# Connectors.net
KiCad netlist of a schematic drawn in Altium Designer
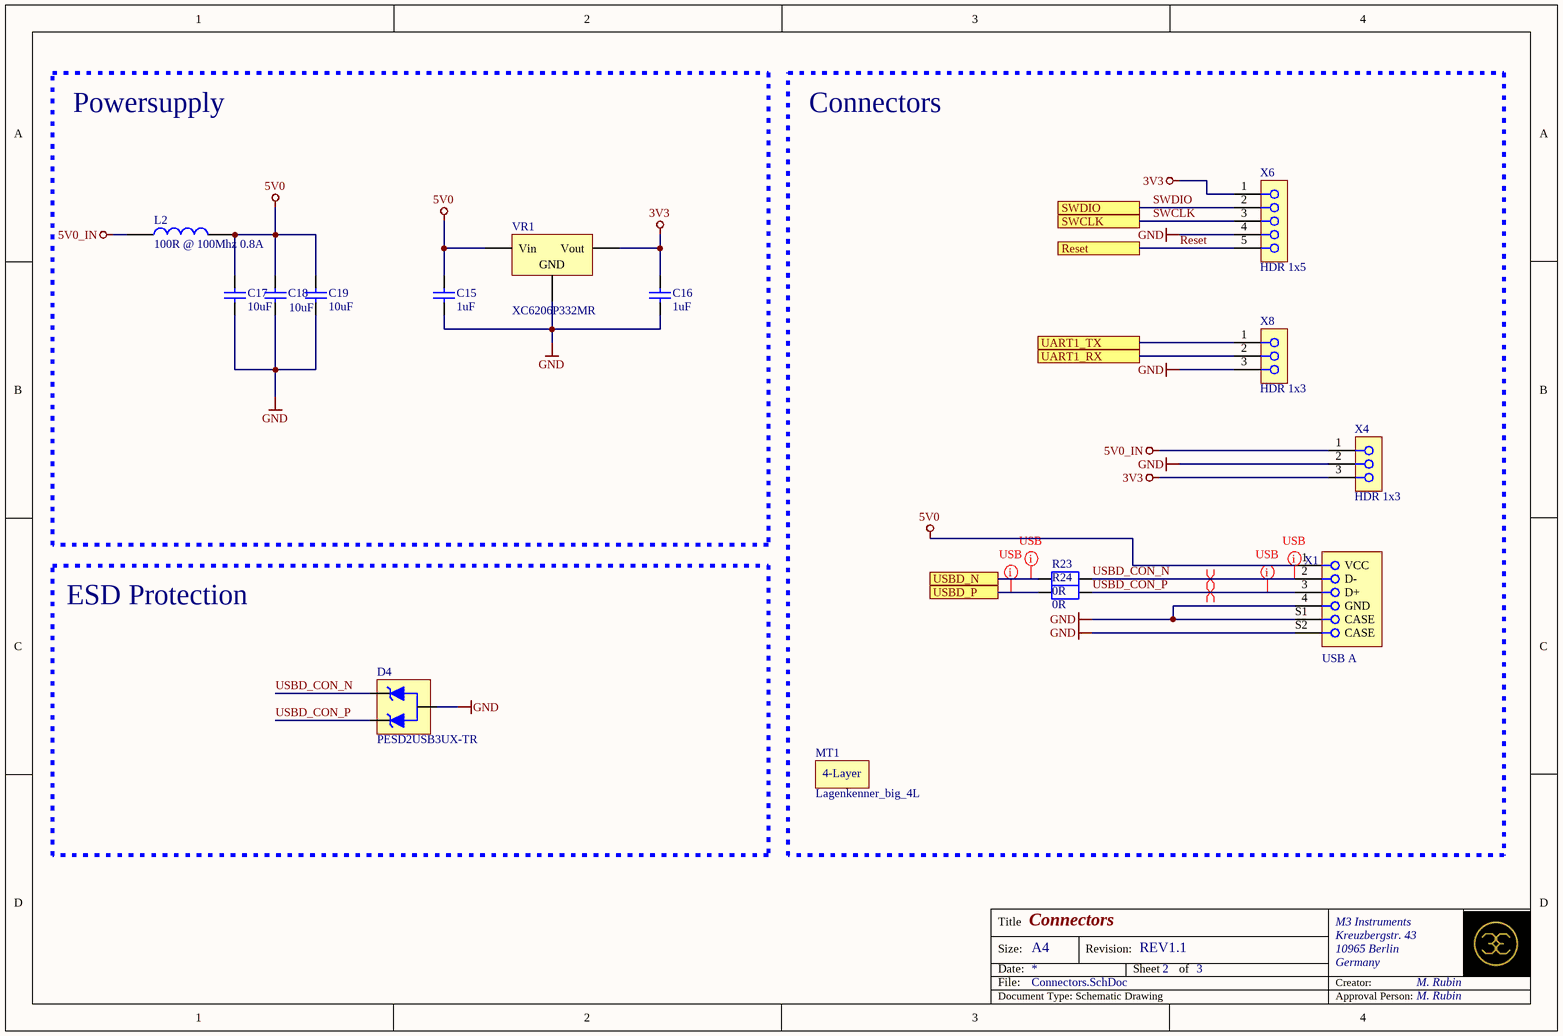
[diagram p0: Connectors.SchDoc]

(export (version "E")
  (design (tool "Eeschema 10.0.6"))
  (components
    (comp (ref "C15")
      (value "1uF")
      (footprint "0603_C")
      (description "Chip capacitors")
      (fields
        (field (name "MANUFACTURER") "Samsung Electro-Mechanics")
        (field (name "PARTNUMBER") "CL10A105KB8NNNC")
      )
      (libsource (lib "Cap") (part "0603 1uF (105) 10% 50V"))
    )
    (comp (ref "C16")
      (value "1uF")
      (footprint "0603_C")
      (description "Chip capacitors")
      (fields
        (field (name "MANUFACTURER") "Samsung Electro-Mechanics")
        (field (name "PARTNUMBER") "CL10A105KB8NNNC")
      )
      (libsource (lib "Cap") (part "0603 1uF (105) 10% 50V"))
    )
    (comp (ref "C17")
      (value "10uF")
      (footprint "0805_C")
      (description "Chip capacitors")
      (fields
        (field (name "MANUFACTURER") "Samsung Electro-Mechanics")
        (field (name "PARTNUMBER") "CL21A106KAYNNNE")
      )
      (libsource (lib "Cap") (part "0805 10uF (106) 10% 25V"))
    )
    (comp (ref "C18")
      (value "10uF")
      (footprint "0805_C")
      (description "Chip capacitors")
      (fields
        (field (name "MANUFACTURER") "Samsung Electro-Mechanics")
        (field (name "PARTNUMBER") "CL21A106KAYNNNE")
      )
      (libsource (lib "Cap") (part "0805 10uF (106) 10% 25V"))
    )
    (comp (ref "C19")
      (value "10uF")
      (footprint "0805_C")
      (description "Chip capacitors")
      (fields
        (field (name "MANUFACTURER") "Samsung Electro-Mechanics")
        (field (name "PARTNUMBER") "CL21A106KAYNNNE")
      )
      (libsource (lib "Cap") (part "0805 10uF (106) 10% 25V"))
    )
    (comp (ref "D4")
      (value "PESD2USB3UX-TR")
      (footprint "SOT95P280X135-3N_123")
      (description "ESD Suppressors / TVS Diodes DIODE ESD PROT")
      (fields (field (name "MANUFACTURER") "Nexperia"))
      (libsource (lib "Diodes") (part "PESD2USB3UX-TR"))
    )
    (comp (ref "L2")
      (value "100R @ 100Mhz 0.8A")
      (footprint "Miscellaneous Devices:6-0805_L")
      (description "Ferrite Bead")
      (libsource (lib "FBEAD") (part "0805 100R@100Mhz 0.8A"))
    )
    (comp (ref "MT1")
      (value "Lagenkenner_big_4L")
      (footprint "Lagenkenner_4L-big")
      (libsource (lib "MISC") (part "Lagenkenner_big_4L"))
    )
    (comp (ref "R23")
      (value "0R")
      (footprint "RESC2012X70N")
      (description "Thick Film Resistors - SMD 1/8watt ZEROohm Jumper")
      (fields
        (field (name "MANUFACTURER") "Vishay")
        (field (name "MANUFACTURER PART NUMBER") "CRCW08050000Z0EA")
      )
      (libsource (lib "Resistors") (part "RES_0R_0805"))
    )
    (comp (ref "R24")
      (value "0R")
      (footprint "RESC2012X70N")
      (description "Thick Film Resistors - SMD 1/8watt ZEROohm Jumper")
      (fields
        (field (name "MANUFACTURER") "Vishay")
        (field (name "MANUFACTURER PART NUMBER") "CRCW08050000Z0EA")
      )
      (libsource (lib "Resistors") (part "RES_0R_0805"))
    )
    (comp (ref "VR1")
      (value "XC6206P332MR")
      (footprint "SOT-23-3L")
      (description "低压差线性稳压(LDO)")
      (libsource (lib "LDO") (part "SOT-23 XC6206P332MR"))
    )
    (comp (ref "X1")
      (value "USB A")
      (footprint "CON_USBA_F_61400416021")
      (description "USB 2.0 Type A Horizontal")
      (fields
        (field (name "MANUFACTURER PART NUMBER") "61400416021")
        (field (name "MANUFACTURER") "WURTH ELEKTRONIK")
      )
      (libsource (lib "Connectors") (part "CON_USB_A_FEMALE"))
    )
    (comp (ref "X4")
      (value "HDR 1x3")
      (footprint "CON_HEADER2.54_1x3W")
      (description "Board-to-Board-Steckverbinder, 2.54 mm, 3 Kontakt(e), Stiftleiste 1-Reihig")
      (fields
        (field (name "MANUFACTURER") "Samtec")
        (field (name "MANUFACTURER PART NUMBER") "TSW-103-07-T-S")
      )
      (libsource (lib "_CONNECTORS") (part "CON_HEADER_1X3"))
    )
    (comp (ref "X6")
      (value "HDR 1x5")
      (footprint "CON_HEADER2.54_1x5W")
      (description "Board-to-Board-Steckverbinder, 2.54 mm, 5 Kontakt(e), Stiftleiste 1-Reihig")
      (fields
        (field (name "MANUFACTURER") "Samtec")
        (field (name "MANUFACTURER PART NUMBER") "TSW-105-07-T-S")
      )
      (libsource (lib "_CONNECTORS") (part "CON_HEADER_1X5"))
    )
    (comp (ref "X8")
      (value "HDR 1x3")
      (footprint "CON_HEADER2.54_1x3W")
      (description "Board-to-Board-Steckverbinder, 2.54 mm, 3 Kontakt(e), Stiftleiste 1-Reihig")
      (fields
        (field (name "MANUFACTURER") "Samtec")
        (field (name "MANUFACTURER PART NUMBER") "TSW-103-07-T-S")
      )
      (libsource (lib "_CONNECTORS") (part "CON_HEADER_1X3"))
    )
  )
  (nets
    (net (code "1") (name "/Reset") (class "Default")
      (node (ref "X6") (pin "5") (pinfunction "5_5") (pintype "passive"))
    )
    (net (code "2") (name "/SWCLK") (class "Default")
      (node (ref "X6") (pin "3") (pinfunction "3_3") (pintype "passive"))
    )
    (net (code "3") (name "/SWDIO") (class "Default")
      (node (ref "X6") (pin "2") (pinfunction "2_2") (pintype "passive"))
    )
    (net (code "4") (name "/UART1_RX") (class "Default")
      (node (ref "X8") (pin "2") (pinfunction "2_2") (pintype "passive"))
    )
    (net (code "5") (name "/UART1_TX") (class "Default")
      (node (ref "X8") (pin "1") (pinfunction "1_1") (pintype "passive"))
    )
    (net (code "6") (name "/USBD_CON_N") (class "Default")
      (node (ref "D4") (pin "1") (pinfunction "1_1") (pintype "passive"))
      (node (ref "R23") (pin "2") (pinfunction "2_2") (pintype "passive"))
      (node (ref "X1") (pin "2") (pinfunction "D-_2") (pintype "passive"))
    )
    (net (code "7") (name "/USBD_CON_P") (class "Default")
      (node (ref "D4") (pin "2") (pinfunction "2_2") (pintype "passive"))
      (node (ref "R24") (pin "2") (pinfunction "2_2") (pintype "passive"))
      (node (ref "X1") (pin "3") (pinfunction "D+_3") (pintype "passive"))
    )
    (net (code "8") (name "/USBD_N") (class "Default")
      (node (ref "R23") (pin "1") (pinfunction "1_1") (pintype "passive"))
    )
    (net (code "9") (name "/USBD_P") (class "Default")
      (node (ref "R24") (pin "1") (pinfunction "1_1") (pintype "passive"))
    )
    (net (code "10") (name "3V3") (class "Default")
      (node (ref "C16") (pin "2") (pinfunction "2_2") (pintype "passive"))
      (node (ref "VR1") (pin "2") (pinfunction "Vout_2") (pintype "passive"))
      (node (ref "X4") (pin "3") (pinfunction "3_3") (pintype "passive"))
      (node (ref "X6") (pin "1") (pinfunction "1_1") (pintype "passive"))
    )
    (net (code "11") (name "5V0") (class "Default")
      (node (ref "C15") (pin "2") (pinfunction "2_2") (pintype "passive"))
      (node (ref "C17") (pin "2") (pinfunction "2_2") (pintype "passive"))
      (node (ref "C18") (pin "2") (pinfunction "2_2") (pintype "passive"))
      (node (ref "C19") (pin "2") (pinfunction "2_2") (pintype "passive"))
      (node (ref "L2") (pin "2") (pinfunction "2_2") (pintype "passive"))
      (node (ref "VR1") (pin "3") (pinfunction "Vin_3") (pintype "passive"))
      (node (ref "X1") (pin "1") (pinfunction "VCC_1") (pintype "passive"))
    )
    (net (code "12") (name "5V0_IN") (class "Default")
      (node (ref "L2") (pin "1") (pinfunction "1_1") (pintype "passive"))
      (node (ref "X4") (pin "1") (pinfunction "1_1") (pintype "passive"))
    )
    (net (code "13") (name "GND") (class "Default")
      (node (ref "C15") (pin "1") (pinfunction "1_1") (pintype "passive"))
      (node (ref "C16") (pin "1") (pinfunction "1_1") (pintype "passive"))
      (node (ref "C17") (pin "1") (pinfunction "1_1") (pintype "passive"))
      (node (ref "C18") (pin "1") (pinfunction "1_1") (pintype "passive"))
      (node (ref "C19") (pin "1") (pinfunction "1_1") (pintype "passive"))
      (node (ref "D4") (pin "3") (pinfunction "3_3") (pintype "passive"))
      (node (ref "VR1") (pin "1") (pinfunction "GND_1") (pintype "passive"))
      (node (ref "X1") (pin "4") (pinfunction "GND_4") (pintype "passive"))
      (node (ref "X1") (pin "S1") (pinfunction "CASE_S1") (pintype "passive"))
      (node (ref "X1") (pin "S2") (pinfunction "CASE_S2") (pintype "passive"))
      (node (ref "X4") (pin "2") (pinfunction "2_2") (pintype "passive"))
      (node (ref "X6") (pin "4") (pinfunction "4_4") (pintype "passive"))
      (node (ref "X8") (pin "3") (pinfunction "3_3") (pintype "passive"))
    )
  )
)
